# JacdacRgbLedBar10_58.net
KiCad netlist of a schematic drawn in Altium Designer
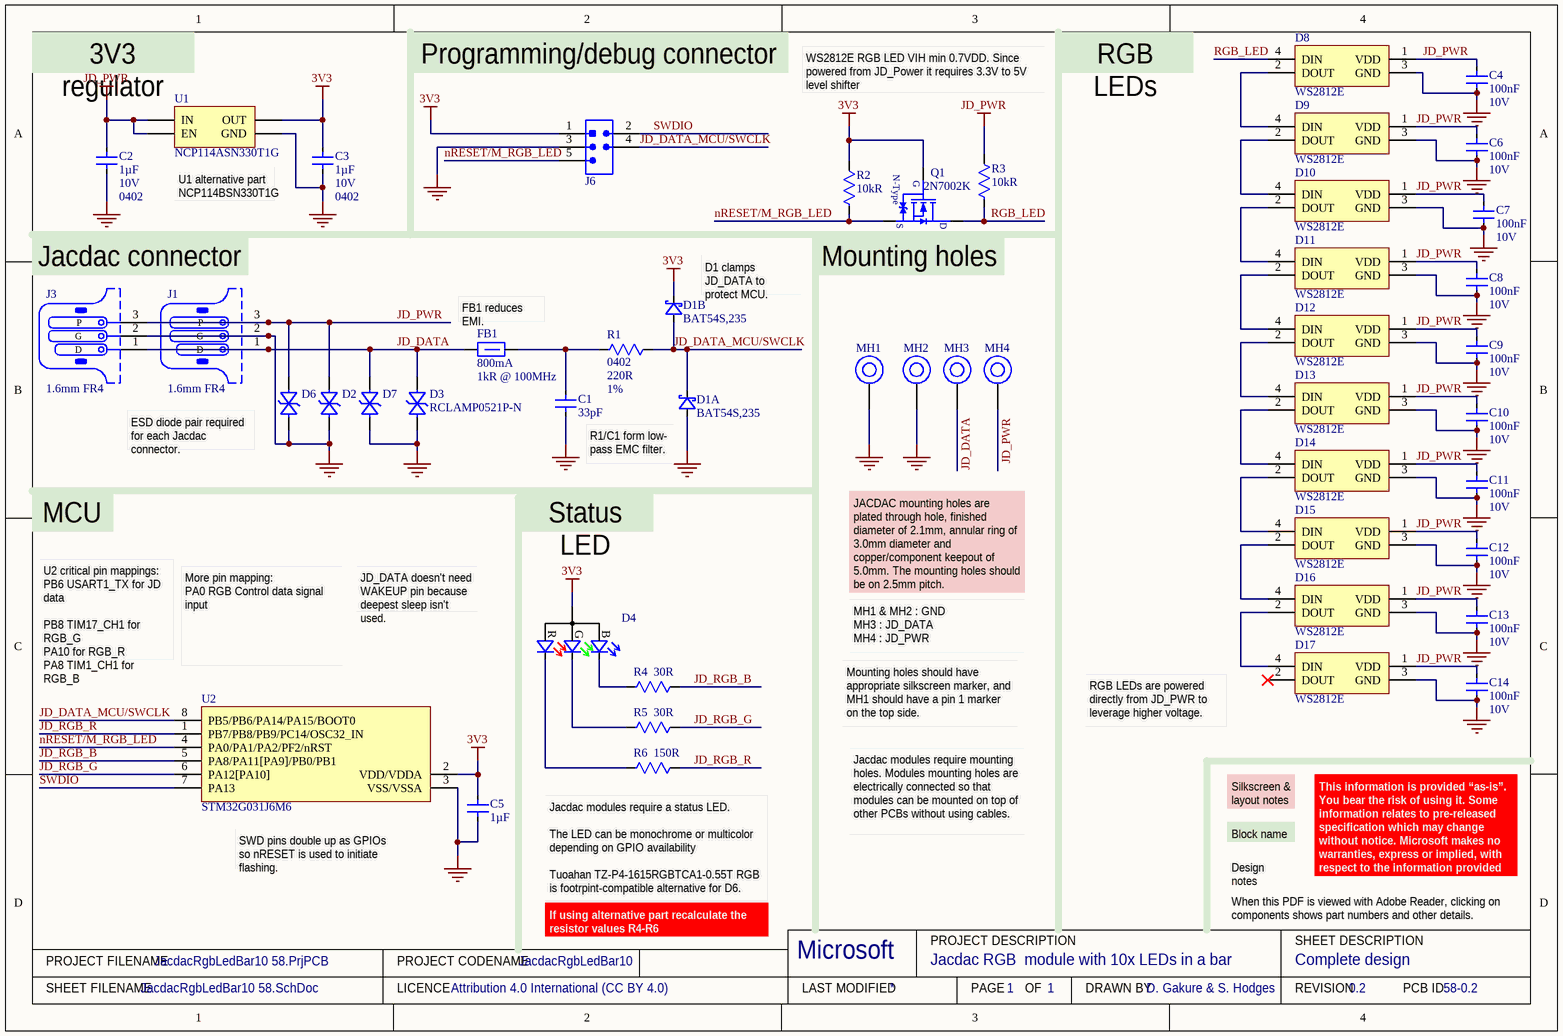
[diagram p0: JacdacRgbLedBar10 58.SchDoc]

(export (version "E")
  (design (tool "Eeschema 10.0.6"))
  (components
    (comp (ref "C1")
      (value "CL05C330JB51PNC")
      (footprint "C0402_0.55MM - without outline")
      (description "CAP CER 33PF 50V NP0 0402")
      (fields
        (field (name "MANUFACTURER") "Samsung")
        (field (name "TOLERANCE") "5%")
        (field (name "CAPACITANCE") "33pF")
        (field (name "CHECKED") "?")
        (field (name "CREATED") "DG")
      )
      (libsource (lib "Samsung") (part "CL05C330JB51PNC"))
    )
    (comp (ref "C2")
      (value "CL05A105KP5NNNC")
      (footprint "C0402_0.55MM - without outline")
      (description "CAP CER 1UF 10V X5R 0402")
      (fields
        (field (name "MANUFACTURER") "Samsung")
        (field (name "TOLERANCE") "10%")
        (field (name "CAPACITANCE") "1µF")
        (field (name "VOLTAGE RATING") "10V")
        (field (name "CASE CODE (IMPERIAL)") "0402")
        (field (name "CREATED") "DG")
        (field (name "CHECKED") "?")
      )
      (libsource (lib "Samsung") (part "CL05A105KP5NNNC"))
    )
    (comp (ref "C3")
      (value "CL05A105KP5NNNC")
      (footprint "C0402_0.55MM - without outline")
      (description "CAP CER 1UF 10V X5R 0402")
      (fields
        (field (name "MANUFACTURER") "Samsung")
        (field (name "TOLERANCE") "10%")
        (field (name "CAPACITANCE") "1µF")
        (field (name "VOLTAGE RATING") "10V")
        (field (name "CASE CODE (IMPERIAL)") "0402")
        (field (name "CREATED") "DG")
        (field (name "CHECKED") "?")
      )
      (libsource (lib "Samsung") (part "CL05A105KP5NNNC"))
    )
    (comp (ref "C4")
      (value "CL05B104KP5NNNC")
      (footprint "C0402_0.55MM - without outline")
      (description "CAP CER 0.1UF 10V X7R 0402")
      (fields
        (field (name "MANUFACTURER") "Samsung")
        (field (name "CAPACITANCE") "100nF")
        (field (name "TOLERANCE") "10%")
        (field (name "VOLTAGE RATING") "10V")
        (field (name "CREATED") "DG")
        (field (name "CHECKED") "?")
      )
      (libsource (lib "Samsung") (part "CL05B104KP5NNNC"))
    )
    (comp (ref "C5")
      (value "CL05A105KP5NNNC")
      (footprint "C0402_0.55MM - without outline")
      (description "CAP CER 1UF 10V X5R 0402")
      (fields
        (field (name "MANUFACTURER") "Samsung")
        (field (name "TOLERANCE") "10%")
        (field (name "CAPACITANCE") "1µF")
        (field (name "CREATED") "DG")
        (field (name "CHECKED") "?")
      )
      (libsource (lib "Samsung") (part "CL05A105KP5NNNC"))
    )
    (comp (ref "C6")
      (value "CL05B104KP5NNNC")
      (footprint "C0402_0.55MM - without outline")
      (description "CAP CER 0.1UF 10V X7R 0402")
      (fields
        (field (name "MANUFACTURER") "Samsung")
        (field (name "CAPACITANCE") "100nF")
        (field (name "TOLERANCE") "10%")
        (field (name "VOLTAGE RATING") "10V")
        (field (name "CREATED") "DG")
        (field (name "CHECKED") "?")
      )
      (libsource (lib "Samsung") (part "CL05B104KP5NNNC"))
    )
    (comp (ref "C7")
      (value "CL05B104KP5NNNC")
      (footprint "C0402_0.55MM - without outline")
      (description "CAP CER 0.1UF 10V X7R 0402")
      (fields
        (field (name "MANUFACTURER") "Samsung")
        (field (name "CAPACITANCE") "100nF")
        (field (name "TOLERANCE") "10%")
        (field (name "VOLTAGE RATING") "10V")
        (field (name "CREATED") "DG")
        (field (name "CHECKED") "?")
      )
      (libsource (lib "Samsung") (part "CL05B104KP5NNNC"))
    )
    (comp (ref "C8")
      (value "CL05B104KP5NNNC")
      (footprint "C0402_0.55MM - without outline")
      (description "CAP CER 0.1UF 10V X7R 0402")
      (fields
        (field (name "MANUFACTURER") "Samsung")
        (field (name "CAPACITANCE") "100nF")
        (field (name "TOLERANCE") "10%")
        (field (name "VOLTAGE RATING") "10V")
        (field (name "CREATED") "DG")
        (field (name "CHECKED") "?")
      )
      (libsource (lib "Samsung") (part "CL05B104KP5NNNC"))
    )
    (comp (ref "C9")
      (value "CL05B104KP5NNNC")
      (footprint "C0402_0.55MM - without outline")
      (description "CAP CER 0.1UF 10V X7R 0402")
      (fields
        (field (name "MANUFACTURER") "Samsung")
        (field (name "CAPACITANCE") "100nF")
        (field (name "TOLERANCE") "10%")
        (field (name "VOLTAGE RATING") "10V")
        (field (name "CREATED") "DG")
        (field (name "CHECKED") "?")
      )
      (libsource (lib "Samsung") (part "CL05B104KP5NNNC"))
    )
    (comp (ref "C10")
      (value "CL05B104KP5NNNC")
      (footprint "C0402_0.55MM - without outline")
      (description "CAP CER 0.1UF 10V X7R 0402")
      (fields
        (field (name "MANUFACTURER") "Samsung")
        (field (name "CAPACITANCE") "100nF")
        (field (name "TOLERANCE") "10%")
        (field (name "VOLTAGE RATING") "10V")
        (field (name "CREATED") "DG")
        (field (name "CHECKED") "?")
      )
      (libsource (lib "Samsung") (part "CL05B104KP5NNNC"))
    )
    (comp (ref "C11")
      (value "CL05B104KP5NNNC")
      (footprint "C0402_0.55MM - without outline")
      (description "CAP CER 0.1UF 10V X7R 0402")
      (fields
        (field (name "MANUFACTURER") "Samsung")
        (field (name "CAPACITANCE") "100nF")
        (field (name "TOLERANCE") "10%")
        (field (name "VOLTAGE RATING") "10V")
        (field (name "CREATED") "DG")
        (field (name "CHECKED") "?")
      )
      (libsource (lib "Samsung") (part "CL05B104KP5NNNC"))
    )
    (comp (ref "C12")
      (value "CL05B104KP5NNNC")
      (footprint "C0402_0.55MM - without outline")
      (description "CAP CER 0.1UF 10V X7R 0402")
      (fields
        (field (name "MANUFACTURER") "Samsung")
        (field (name "CAPACITANCE") "100nF")
        (field (name "TOLERANCE") "10%")
        (field (name "VOLTAGE RATING") "10V")
        (field (name "CREATED") "DG")
        (field (name "CHECKED") "?")
      )
      (libsource (lib "Samsung") (part "CL05B104KP5NNNC"))
    )
    (comp (ref "C13")
      (value "CL05B104KP5NNNC")
      (footprint "C0402_0.55MM - without outline")
      (description "CAP CER 0.1UF 10V X7R 0402")
      (fields
        (field (name "MANUFACTURER") "Samsung")
        (field (name "CAPACITANCE") "100nF")
        (field (name "TOLERANCE") "10%")
        (field (name "VOLTAGE RATING") "10V")
        (field (name "CREATED") "DG")
        (field (name "CHECKED") "?")
      )
      (libsource (lib "Samsung") (part "CL05B104KP5NNNC"))
    )
    (comp (ref "C14")
      (value "CL05B104KP5NNNC")
      (footprint "C0402_0.55MM - without outline")
      (description "CAP CER 0.1UF 10V X7R 0402")
      (fields
        (field (name "MANUFACTURER") "Samsung")
        (field (name "CAPACITANCE") "100nF")
        (field (name "TOLERANCE") "10%")
        (field (name "VOLTAGE RATING") "10V")
        (field (name "CREATED") "DG")
        (field (name "CHECKED") "?")
      )
      (libsource (lib "Samsung") (part "CL05B104KP5NNNC"))
    )
    (comp (ref "D1")
      (value "BAT54S")
      (footprint "NXP-BAT54S-TO-236AB - without outline")
      (description "DIODE ARRAY SCHOTTKY 30V SOT23")
      (fields (field (name "MANUFACTURER") "Nexperia") (field (name "MANUFACTURER PART NUMBER") "BAT54S,235"))
      (libsource (lib "NXP") (part "BAT54S"))
    )
    (comp (ref "D2")
      (value "RCLAMP0521P-N")
      (footprint "TVS 0402 - without outline")
      (description "Bidirectional 5V (Max) 6V 16V 3.5A (8/20us) 0402 TVS RoHS")
      (fields
        (field (name "MANUFACTURER") "Born Semiconductor")
        (field (name "CREATED BY") "D Gakure")
        (field (name "CHECKED BY") "?")
      )
      (libsource (lib "BornSemiconductor") (part "RCLAMP0521P-N"))
    )
    (comp (ref "D3")
      (value "RCLAMP0521P-N")
      (footprint "TVS 0402 - without outline")
      (description "Bidirectional 5V (Max) 6V 16V 3.5A (8/20us) 0402 TVS RoHS")
      (fields
        (field (name "MANUFACTURER") "Born Semiconductor")
        (field (name "MANUFACTURER PART NUMBER") "RCLAMP0521P-N")
        (field (name "CREATED BY") "D Gakure")
        (field (name "CHECKED BY") "?")
      )
      (libsource (lib "BornSemiconductor") (part "RCLAMP0521P-N"))
    )
    (comp (ref "D4")
      (value "TZ-P4-1615RGBTCA1-0.55T")
      (footprint "TZ-P4-1615RGBTCA1-0.55T")
      (description "1615 Light Emitting Diodes (LED) RoHS")
      (fields
        (field (name "MANUFACTURER") "TUOZHAN")
        (field (name "CREATED BY") "D. Gakure")
        (field (name "CHECKED BY") "?")
      )
      (libsource (lib "Tuozhan") (part "TZ-P4-1615RGBTCA1-0.55T"))
    )
    (comp (ref "D6")
      (value "RCLAMP0521P-N")
      (footprint "TVS 0402 - without outline")
      (description "Bidirectional 5V (Max) 6V 16V 3.5A (8/20us) 0402 TVS RoHS")
      (fields
        (field (name "MANUFACTURER") "Born Semiconductor")
        (field (name "CREATED BY") "D Gakure")
        (field (name "CHECKED BY") "?")
      )
      (libsource (lib "BornSemiconductor") (part "RCLAMP0521P-N"))
    )
    (comp (ref "D7")
      (value "RCLAMP0521P-N")
      (footprint "TVS 0402 - without outline")
      (description "Bidirectional 5V (Max) 6V 16V 3.5A (8/20us) 0402 TVS RoHS")
      (fields
        (field (name "MANUFACTURER") "Born Semiconductor")
        (field (name "CREATED BY") "D Gakure")
        (field (name "CHECKED BY") "?")
      )
      (libsource (lib "BornSemiconductor") (part "RCLAMP0521P-N"))
    )
    (comp (ref "D8")
      (value "WS2812E")
      (footprint "WS2812E-5050")
      (description "WS2812E 5050 RGB LED WITH INTEGRATED DRIVER")
      (fields (field (name "MANUFACTURER") "Worldsemi") (field (name "MANUFACTURER PART NUMBER") "WS2812E"))
      (libsource (lib "WorldSemi") (part "WS2812E-5050"))
    )
    (comp (ref "D9")
      (value "WS2812E")
      (footprint "WS2812E-5050")
      (description "WS2812E 5050 RGB LED WITH INTEGRATED DRIVER")
      (fields (field (name "MANUFACTURER") "Worldsemi") (field (name "MANUFACTURER PART NUMBER") "WS2812E"))
      (libsource (lib "WorldSemi") (part "WS2812E-5050"))
    )
    (comp (ref "D10")
      (value "WS2812E")
      (footprint "WS2812E-5050")
      (description "WS2812E 5050 RGB LED WITH INTEGRATED DRIVER")
      (fields (field (name "MANUFACTURER") "Worldsemi") (field (name "MANUFACTURER PART NUMBER") "WS2812E"))
      (libsource (lib "WorldSemi") (part "WS2812E-5050"))
    )
    (comp (ref "D11")
      (value "WS2812E")
      (footprint "WS2812E-5050")
      (description "WS2812E 5050 RGB LED WITH INTEGRATED DRIVER")
      (fields (field (name "MANUFACTURER") "Worldsemi") (field (name "MANUFACTURER PART NUMBER") "WS2812E"))
      (libsource (lib "WorldSemi") (part "WS2812E-5050"))
    )
    (comp (ref "D12")
      (value "WS2812E")
      (footprint "WS2812E-5050")
      (description "WS2812E 5050 RGB LED WITH INTEGRATED DRIVER")
      (fields (field (name "MANUFACTURER") "Worldsemi") (field (name "MANUFACTURER PART NUMBER") "WS2812E"))
      (libsource (lib "WorldSemi") (part "WS2812E-5050"))
    )
    (comp (ref "D13")
      (value "WS2812E")
      (footprint "WS2812E-5050")
      (description "WS2812E 5050 RGB LED WITH INTEGRATED DRIVER")
      (fields (field (name "MANUFACTURER") "Worldsemi") (field (name "MANUFACTURER PART NUMBER") "WS2812E"))
      (libsource (lib "WorldSemi") (part "WS2812E-5050"))
    )
    (comp (ref "D14")
      (value "WS2812E")
      (footprint "WS2812E-5050")
      (description "WS2812E 5050 RGB LED WITH INTEGRATED DRIVER")
      (fields (field (name "MANUFACTURER") "Worldsemi") (field (name "MANUFACTURER PART NUMBER") "WS2812E"))
      (libsource (lib "WorldSemi") (part "WS2812E-5050"))
    )
    (comp (ref "D15")
      (value "WS2812E")
      (footprint "WS2812E-5050")
      (description "WS2812E 5050 RGB LED WITH INTEGRATED DRIVER")
      (fields (field (name "MANUFACTURER") "Worldsemi") (field (name "MANUFACTURER PART NUMBER") "WS2812E"))
      (libsource (lib "WorldSemi") (part "WS2812E-5050"))
    )
    (comp (ref "D16")
      (value "WS2812E")
      (footprint "WS2812E-5050")
      (description "WS2812E 5050 RGB LED WITH INTEGRATED DRIVER")
      (fields (field (name "MANUFACTURER") "Worldsemi") (field (name "MANUFACTURER PART NUMBER") "WS2812E"))
      (libsource (lib "WorldSemi") (part "WS2812E-5050"))
    )
    (comp (ref "D17")
      (value "WS2812E")
      (footprint "WS2812E-5050")
      (description "WS2812E 5050 RGB LED WITH INTEGRATED DRIVER")
      (fields (field (name "MANUFACTURER") "Worldsemi") (field (name "MANUFACTURER PART NUMBER") "WS2812E"))
      (libsource (lib "WorldSemi") (part "WS2812E-5050"))
    )
    (comp (ref "FB1")
      (value "TDK MPZ1608S102ATA00")
      (footprint "TDK MPZ1608 0.8mm - without outline")
      (description "0603 1k@100MHz 0.8A chip")
      (fields
        (field (name "TOLERANCE") "25%")
        (field (name "MANUFACTURER") "TDK")
        (field (name "CURRENT RATING") "800mA")
        (field (name "IMPEDANCE") "1kR @ 100MHz")
      )
      (libsource (lib "TDK") (part "TDK MPZ1608S102ATA00"))
    )
    (comp (ref "J1")
      (value "3 pin JACDAC edge connector")
      (footprint "JACDAC_EDGE_CONNECTOR_NO_TRACES")
      (description "3 pin JACDAC edge connector 1.27mm pitch")
      (fields
        (field (name "MANUFACTURER PART NUMBER") "JACDAC_EDGE_CONNECTOR")
        (field (name "PCB TYPE") "1.6mm FR4")
        (field (name "CHECKED BY") "?")
        (field (name "CREATED BY") "D. Gakure")
      )
      (libsource (lib "generic-con") (part "Jacdac edge connector"))
    )
    (comp (ref "J3")
      (value "3 pin JACDAC edge connector")
      (footprint "JACDAC_EDGE_CONNECTOR_NO_TRACES")
      (description "3 pin JACDAC edge connector 1.27mm pitch")
      (fields
        (field (name "MANUFACTURER PART NUMBER") "JACDAC_EDGE_CONNECTOR")
        (field (name "PCB TYPE") "1.6mm FR4")
        (field (name "CHECKED BY") "?")
        (field (name "CREATED BY") "D. Gakure")
      )
      (libsource (lib "generic-con") (part "Jacdac edge connector"))
    )
    (comp (ref "J6")
      (value "Hack Connect Mini 1.27 mm pitch 2-row")
      (footprint "HACK_CONNECT_MINI_5_X_1_27")
      (libsource (lib "HackConnect") (part "HACK_CONNECT_MINI"))
    )
    (comp (ref "MH1")
      (value "MH_5.0MMK_3.0MMC_2.1MMD_PTH")
      (footprint "MH_5.0MMK_3.0MMC_2.1MMD_PTH:MH_5.0MMK_3.0MMC_2.1MMD_PTH")
      (description "Mounting Hole 5.0mm keepout, 3.0mm annualar ring and 2.1mm Drill PTH")
      (libsource (lib "generic") (part "MH_5.0MMK_3.0MMC_2.1MMD_PTH"))
    )
    (comp (ref "MH2")
      (value "MH_5.0MMK_3.0MMC_2.1MMD_PTH")
      (footprint "MH_5.0MMK_3.0MMC_2.1MMD_PTH:MH_5.0MMK_3.0MMC_2.1MMD_PTH")
      (description "Mounting Hole 5.0mm keepout, 3.0mm annualar ring and 2.1mm Drill PTH")
      (libsource (lib "generic") (part "MH_5.0MMK_3.0MMC_2.1MMD_PTH"))
    )
    (comp (ref "MH3")
      (value "MH_5.0MMK_3.0MMC_2.1MMD_PTH")
      (footprint "MH_5.0MMK_3.0MMC_2.1MMD_PTH:MH_5.0MMK_3.0MMC_2.1MMD_PTH")
      (description "Mounting Hole 5.0mm keepout, 3.0mm annualar ring and 2.1mm Drill PTH")
      (libsource (lib "generic") (part "MH_5.0MMK_3.0MMC_2.1MMD_PTH"))
    )
    (comp (ref "MH4")
      (value "MH_5.0MMK_3.0MMC_2.1MMD_PTH")
      (footprint "MH_5.0MMK_3.0MMC_2.1MMD_PTH")
      (description "Mounting Hole 5.0mm keepout, 3.0mm annualar ring and 2.1mm Drill PTH")
      (libsource (lib "generic") (part "MH_5.0MMK_3.0MMC_2.1MMD_PTH"))
    )
    (comp (ref "Q1")
      (value "2N7002K")
      (footprint "SOT-23")
      (description "MOSFET Transistor, N Channel, 300 mA, 60 V, 2 ohm, 10 V, 2.5 V")
      (fields
        (field (name "MANUFACTURER") "ON Semiconductor / Fairchild")
        (field (name "VOLTAGE") "60V")
        (field (name "MANUFACTURER PART NUMBER") "2N7002K")
        (field (name "CREATED BY") "D. Gakure")
        (field (name "CHECKED BY") "?")
      )
      (libsource (lib "OnSemiconductor") (part "2N7002K (2)"))
    )
    (comp (ref "R1")
      (value "RC0402FR-07220RL")
      (footprint "R0402 - Without outline")
      (description "RES SMD 220 OHM 1% 1/16W 0402")
      (fields
        (field (name "MANUFACTURER") "Yageo")
        (field (name "CASE CODE (IMPERIAL)") "0402")
        (field (name "RESISTANCE") "220R")
        (field (name "TOLERANCE") "1%")
        (field (name "CREATED") "D.G")
        (field (name "CHECKED") "?")
      )
      (libsource (lib "Yageo") (part "RC0402FR-07220RL"))
    )
    (comp (ref "R2")
      (value "10k")
      (footprint "R0402 - Without outline")
      (description "RES SMD 10K OHM 1% 1/16W 0402")
      (fields
        (field (name "MANUFACTURER") "Yageo")
        (field (name "MANUFACTURER PART NUMBER") "RC0402FR-0710KL")
        (field (name "RESISTANCE") "10kR")
        (field (name "CHECKED") "?")
        (field (name "CREATED") "DG")
      )
      (libsource (lib "Yageo") (part "RC0402FR-0710KL"))
    )
    (comp (ref "R3")
      (value "10k")
      (footprint "R0402 - Without outline")
      (description "RES SMD 10K OHM 1% 1/16W 0402")
      (fields
        (field (name "MANUFACTURER") "Yageo")
        (field (name "MANUFACTURER PART NUMBER") "RC0402FR-0710KL")
        (field (name "RESISTANCE") "10kR")
        (field (name "CHECKED") "?")
        (field (name "CREATED") "DG")
      )
      (libsource (lib "Yageo") (part "RC0402FR-0710KL"))
    )
    (comp (ref "R4")
      (value "RC0402FR-0730RL")
      (footprint "R0402 - Without outline")
      (description "RES SMD 30 OHM 1% 1/16W 0402")
      (fields
        (field (name "MANUFACTURER") "Yageo")
        (field (name "RESISTANCE") "30R")
        (field (name "TOLERANCE") "1%")
        (field (name "CREATED BY") "D. Gakure")
        (field (name "CHECKED BY") "?")
      )
      (libsource (lib "Yageo") (part "RC0402FR-0730RL"))
    )
    (comp (ref "R5")
      (value "RC0402FR-0730RL")
      (footprint "R0402 - Without outline")
      (description "RES SMD 30 OHM 1% 1/16W 0402")
      (fields
        (field (name "MANUFACTURER") "Yageo")
        (field (name "RESISTANCE") "30R")
        (field (name "TOLERANCE") "1%")
        (field (name "CREATED BY") "D. Gakure")
        (field (name "CHECKED BY") "?")
      )
      (libsource (lib "Yageo") (part "RC0402FR-0730RL"))
    )
    (comp (ref "R6")
      (value "RC0402FR-07150RL")
      (footprint "R0402 - Without outline")
      (description "RES SMD 150 OHM 1% 1/16W 0402")
      (fields
        (field (name "MANUFACTURER") "Yageo")
        (field (name "RESISTANCE") "150R")
        (field (name "TOLERANCE") "1%")
        (field (name "CREATED BY") "D. Gakure")
        (field (name "CHECKED BY") "?")
      )
      (libsource (lib "Yageo") (part "RC0402FR-07150RL"))
    )
    (comp (ref "U1")
      (value "LDO 3.3V/300 mA")
      (footprint "ON_SEMI-SOT23-5 - without outline")
      (fields
        (field (name "MANUFACTURER") "ON Semiconductor")
        (field (name "MANUFACTURER PART NUMBER") "NCP114ASN330T1G")
        (field (name "CREATED") "DG")
        (field (name "CHECKED") "?")
      )
      (libsource (lib "OnSemiconductor") (part "NCP114ASN330T1G"))
    )
    (comp (ref "U2")
      (value "STM32G031J6M6")
      (footprint "8-SOIC")
      (description "MCU 32-bit ARM Cortex M0+ RISC 32KB Flash 2.5V/3.3V 8-Pin SO N Tube")
      (fields
        (field (name "MANUFACTURER") "STMicroelectronics")
        (field (name "MANUFACTURER PART NUMBER") "STM32G031J6M6")
        (field (name "CREATED BY") "D. Gakure")
        (field (name "CHECKED BY") "?")
      )
      (libsource (lib "ST") (part "STM32G031J6M6"))
    )
  )
  (nets
    (net (code "1") (name "/JD_DATA") (class "Default")
      (node (ref "D3") (pin "1") (pinfunction "K_1") (pintype "passive"))
      (node (ref "D7") (pin "1") (pinfunction "K_1") (pintype "passive"))
      (node (ref "FB1") (pin "1") (pinfunction "1_1") (pintype "passive"))
      (node (ref "J1") (pin "1") (pinfunction "D_1") (pintype "passive"))
      (node (ref "J3") (pin "1") (pinfunction "D_1") (pintype "passive"))
      (node (ref "MH3") (pin "1") (pinfunction "1_1") (pintype "passive"))
    )
    (net (code "2") (name "/JD_DATA_MCU{slash}SWCLK") (class "Default")
      (node (ref "D1") (pin "3") (pinfunction "A_3") (pintype "passive"))
      (node (ref "J6") (pin "4") (pinfunction "SWCLK_4") (pintype "passive"))
      (node (ref "R1") (pin "1") (pinfunction "1_1") (pintype "passive"))
      (node (ref "U2") (pin "8") (pinfunction "PB5/PB6/PA14/PA15/BOOT0_8") (pintype "passive"))
    )
    (net (code "3") (name "/JD_RGB_B") (class "Default")
      (node (ref "R4") (pin "2") (pinfunction "2_2") (pintype "passive"))
      (node (ref "U2") (pin "5") (pinfunction "PA8/PA11[PA9]/PB0/PB1_5") (pintype "passive"))
    )
    (net (code "4") (name "/JD_RGB_G") (class "Default")
      (node (ref "R5") (pin "2") (pinfunction "2_2") (pintype "passive"))
      (node (ref "U2") (pin "6") (pinfunction "PA12[PA10]_6") (pintype "passive"))
    )
    (net (code "5") (name "/JD_RGB_R") (class "Default")
      (node (ref "R6") (pin "2") (pinfunction "2_2") (pintype "passive"))
      (node (ref "U2") (pin "1") (pinfunction "PB7/PB8/PB9/PC14/OSC32_IN_1") (pintype "passive"))
    )
    (net (code "6") (name "/RGB_LED") (class "Default")
      (node (ref "D8") (pin "4") (pinfunction "DIN_4") (pintype "passive"))
      (node (ref "Q1") (pin "3") (pinfunction "D_3") (pintype "passive"))
      (node (ref "R3") (pin "2") (pinfunction "2_2") (pintype "passive"))
    )
    (net (code "7") (name "/SWDIO") (class "Default")
      (node (ref "J6") (pin "2") (pinfunction "SWDIO_2") (pintype "passive"))
      (node (ref "U2") (pin "7") (pinfunction "PA13_7") (pintype "passive"))
    )
    (net (code "8") (name "/nRESET{slash}M_RGB_LED") (class "Default")
      (node (ref "J6") (pin "5") (pinfunction "RESET_5") (pintype "passive"))
      (node (ref "Q1") (pin "2") (pinfunction "S_2") (pintype "passive"))
      (node (ref "R2") (pin "2") (pinfunction "2_2") (pintype "passive"))
      (node (ref "U2") (pin "4") (pinfunction "PA0/PA1/PA2/PF2/nRST_4") (pintype "passive"))
    )
    (net (code "9") (name "3V3") (class "Default")
      (node (ref "C3") (pin "2") (pinfunction "2_2") (pintype "passive"))
      (node (ref "C5") (pin "2") (pinfunction "2_2") (pintype "passive"))
      (node (ref "D1") (pin "2") (pinfunction "K_2") (pintype "passive"))
      (node (ref "D4") (pin "1") (pinfunction "A_1") (pintype "passive"))
      (node (ref "J6") (pin "1") (pinfunction "VCC_1") (pintype "passive"))
      (node (ref "Q1") (pin "1") (pinfunction "G_1") (pintype "passive"))
      (node (ref "R2") (pin "1") (pinfunction "1_1") (pintype "passive"))
      (node (ref "U1") (pin "5") (pinfunction "OUT_5") (pintype "passive"))
      (node (ref "U2") (pin "2") (pinfunction "VDD/VDDA_2") (pintype "passive"))
    )
    (net (code "10") (name "GND") (class "Default")
      (node (ref "C1") (pin "1") (pinfunction "1_1") (pintype "passive"))
      (node (ref "C10") (pin "1") (pinfunction "1_1") (pintype "passive"))
      (node (ref "C11") (pin "1") (pinfunction "1_1") (pintype "passive"))
      (node (ref "C12") (pin "1") (pinfunction "1_1") (pintype "passive"))
      (node (ref "C13") (pin "1") (pinfunction "1_1") (pintype "passive"))
      (node (ref "C14") (pin "1") (pinfunction "1_1") (pintype "passive"))
      (node (ref "C2") (pin "1") (pinfunction "1_1") (pintype "passive"))
      (node (ref "C3") (pin "1") (pinfunction "1_1") (pintype "passive"))
      (node (ref "C4") (pin "1") (pinfunction "1_1") (pintype "passive"))
      (node (ref "C5") (pin "1") (pinfunction "1_1") (pintype "passive"))
      (node (ref "C6") (pin "1") (pinfunction "1_1") (pintype "passive"))
      (node (ref "C7") (pin "1") (pinfunction "1_1") (pintype "passive"))
      (node (ref "C8") (pin "1") (pinfunction "1_1") (pintype "passive"))
      (node (ref "C9") (pin "1") (pinfunction "1_1") (pintype "passive"))
      (node (ref "D1") (pin "1") (pinfunction "A_1") (pintype "passive"))
      (node (ref "D10") (pin "3") (pinfunction "GND_3") (pintype "passive"))
      (node (ref "D11") (pin "3") (pinfunction "GND_3") (pintype "passive"))
      (node (ref "D12") (pin "3") (pinfunction "GND_3") (pintype "passive"))
      (node (ref "D13") (pin "3") (pinfunction "GND_3") (pintype "passive"))
      (node (ref "D14") (pin "3") (pinfunction "GND_3") (pintype "passive"))
      (node (ref "D15") (pin "3") (pinfunction "GND_3") (pintype "passive"))
      (node (ref "D16") (pin "3") (pinfunction "GND_3") (pintype "passive"))
      (node (ref "D17") (pin "3") (pinfunction "GND_3") (pintype "passive"))
      (node (ref "D2") (pin "2") (pinfunction "A_2") (pintype "passive"))
      (node (ref "D3") (pin "2") (pinfunction "A_2") (pintype "passive"))
      (node (ref "D6") (pin "2") (pinfunction "A_2") (pintype "passive"))
      (node (ref "D7") (pin "2") (pinfunction "A_2") (pintype "passive"))
      (node (ref "D8") (pin "3") (pinfunction "GND_3") (pintype "passive"))
      (node (ref "D9") (pin "3") (pinfunction "GND_3") (pintype "passive"))
      (node (ref "J1") (pin "2") (pinfunction "G_2") (pintype "passive"))
      (node (ref "J3") (pin "2") (pinfunction "G_2") (pintype "passive"))
      (node (ref "J6") (pin "3") (pinfunction "GND_3") (pintype "passive"))
      (node (ref "MH1") (pin "1") (pinfunction "1_1") (pintype "passive"))
      (node (ref "MH2") (pin "1") (pinfunction "1_1") (pintype "passive"))
      (node (ref "U1") (pin "2") (pinfunction "GND_2") (pintype "passive"))
      (node (ref "U2") (pin "3") (pinfunction "VSS/VSSA_3") (pintype "passive"))
    )
    (net (code "11") (name "JD_PWR") (class "Default")
      (node (ref "C10") (pin "2") (pinfunction "2_2") (pintype "passive"))
      (node (ref "C11") (pin "2") (pinfunction "2_2") (pintype "passive"))
      (node (ref "C12") (pin "2") (pinfunction "2_2") (pintype "passive"))
      (node (ref "C13") (pin "2") (pinfunction "2_2") (pintype "passive"))
      (node (ref "C14") (pin "2") (pinfunction "2_2") (pintype "passive"))
      (node (ref "C2") (pin "2") (pinfunction "2_2") (pintype "passive"))
      (node (ref "C4") (pin "2") (pinfunction "2_2") (pintype "passive"))
      (node (ref "C6") (pin "2") (pinfunction "2_2") (pintype "passive"))
      (node (ref "C7") (pin "2") (pinfunction "2_2") (pintype "passive"))
      (node (ref "C8") (pin "2") (pinfunction "2_2") (pintype "passive"))
      (node (ref "C9") (pin "2") (pinfunction "2_2") (pintype "passive"))
      (node (ref "D10") (pin "1") (pinfunction "VDD_1") (pintype "passive"))
      (node (ref "D11") (pin "1") (pinfunction "VDD_1") (pintype "passive"))
      (node (ref "D12") (pin "1") (pinfunction "VDD_1") (pintype "passive"))
      (node (ref "D13") (pin "1") (pinfunction "VDD_1") (pintype "passive"))
      (node (ref "D14") (pin "1") (pinfunction "VDD_1") (pintype "passive"))
      (node (ref "D15") (pin "1") (pinfunction "VDD_1") (pintype "passive"))
      (node (ref "D16") (pin "1") (pinfunction "VDD_1") (pintype "passive"))
      (node (ref "D17") (pin "1") (pinfunction "VDD_1") (pintype "passive"))
      (node (ref "D2") (pin "1") (pinfunction "K_1") (pintype "passive"))
      (node (ref "D6") (pin "1") (pinfunction "K_1") (pintype "passive"))
      (node (ref "D8") (pin "1") (pinfunction "VDD_1") (pintype "passive"))
      (node (ref "D9") (pin "1") (pinfunction "VDD_1") (pintype "passive"))
      (node (ref "J1") (pin "3") (pinfunction "P_3") (pintype "passive"))
      (node (ref "J3") (pin "3") (pinfunction "P_3") (pintype "passive"))
      (node (ref "MH4") (pin "1") (pinfunction "1_1") (pintype "passive"))
      (node (ref "R3") (pin "1") (pinfunction "1_1") (pintype "passive"))
      (node (ref "U1") (pin "1") (pinfunction "IN_1") (pintype "passive"))
      (node (ref "U1") (pin "3") (pinfunction "EN_3") (pintype "passive"))
    )
    (net (code "12") (name "Net-(C1-Pad2)") (class "Default")
      (node (ref "C1") (pin "2") (pinfunction "2_2") (pintype "passive"))
      (node (ref "FB1") (pin "2") (pinfunction "2_2") (pintype "passive"))
      (node (ref "R1") (pin "2") (pinfunction "2_2") (pintype "passive"))
    )
    (net (code "13") (name "Net-(D4-B)") (class "Default")
      (node (ref "D4") (pin "4") (pinfunction "B_4") (pintype "passive"))
      (node (ref "R4") (pin "1") (pinfunction "1_1") (pintype "passive"))
    )
    (net (code "14") (name "Net-(D4-G)") (class "Default")
      (node (ref "D4") (pin "3") (pinfunction "G_3") (pintype "passive"))
      (node (ref "R5") (pin "1") (pinfunction "1_1") (pintype "passive"))
    )
    (net (code "15") (name "Net-(D4-R)") (class "Default")
      (node (ref "D4") (pin "2") (pinfunction "R_2") (pintype "passive"))
      (node (ref "R6") (pin "1") (pinfunction "1_1") (pintype "passive"))
    )
    (net (code "16") (name "Net-(D8-DOUT)") (class "Default")
      (node (ref "D8") (pin "2") (pinfunction "DOUT_2") (pintype "passive"))
      (node (ref "D9") (pin "4") (pinfunction "DIN_4") (pintype "passive"))
    )
    (net (code "17") (name "Net-(D10-DIN)") (class "Default")
      (node (ref "D10") (pin "4") (pinfunction "DIN_4") (pintype "passive"))
      (node (ref "D9") (pin "2") (pinfunction "DOUT_2") (pintype "passive"))
    )
    (net (code "18") (name "Net-(D10-DOUT)") (class "Default")
      (node (ref "D10") (pin "2") (pinfunction "DOUT_2") (pintype "passive"))
      (node (ref "D11") (pin "4") (pinfunction "DIN_4") (pintype "passive"))
    )
    (net (code "19") (name "Net-(D11-DOUT)") (class "Default")
      (node (ref "D11") (pin "2") (pinfunction "DOUT_2") (pintype "passive"))
      (node (ref "D12") (pin "4") (pinfunction "DIN_4") (pintype "passive"))
    )
    (net (code "20") (name "Net-(D12-DOUT)") (class "Default")
      (node (ref "D12") (pin "2") (pinfunction "DOUT_2") (pintype "passive"))
      (node (ref "D13") (pin "4") (pinfunction "DIN_4") (pintype "passive"))
    )
    (net (code "21") (name "Net-(D13-DOUT)") (class "Default")
      (node (ref "D13") (pin "2") (pinfunction "DOUT_2") (pintype "passive"))
      (node (ref "D14") (pin "4") (pinfunction "DIN_4") (pintype "passive"))
    )
    (net (code "22") (name "Net-(D14-DOUT)") (class "Default")
      (node (ref "D14") (pin "2") (pinfunction "DOUT_2") (pintype "passive"))
      (node (ref "D15") (pin "4") (pinfunction "DIN_4") (pintype "passive"))
    )
    (net (code "23") (name "Net-(D15-DOUT)") (class "Default")
      (node (ref "D15") (pin "2") (pinfunction "DOUT_2") (pintype "passive"))
      (node (ref "D16") (pin "4") (pinfunction "DIN_4") (pintype "passive"))
    )
    (net (code "24") (name "Net-(D16-DOUT)") (class "Default")
      (node (ref "D16") (pin "2") (pinfunction "DOUT_2") (pintype "passive"))
      (node (ref "D17") (pin "4") (pinfunction "DIN_4") (pintype "passive"))
    )
    (net (code "25") (name "unconnected-(D17-DOUT-Pad2)") (class "Default")
      (node (ref "D17") (pin "2") (pinfunction "DOUT_2") (pintype "passive+no_connect"))
    )
  )
)
